# 03_-_POWER_SUPPLIES.net
KiCad netlist of a schematic drawn in Altium Designer
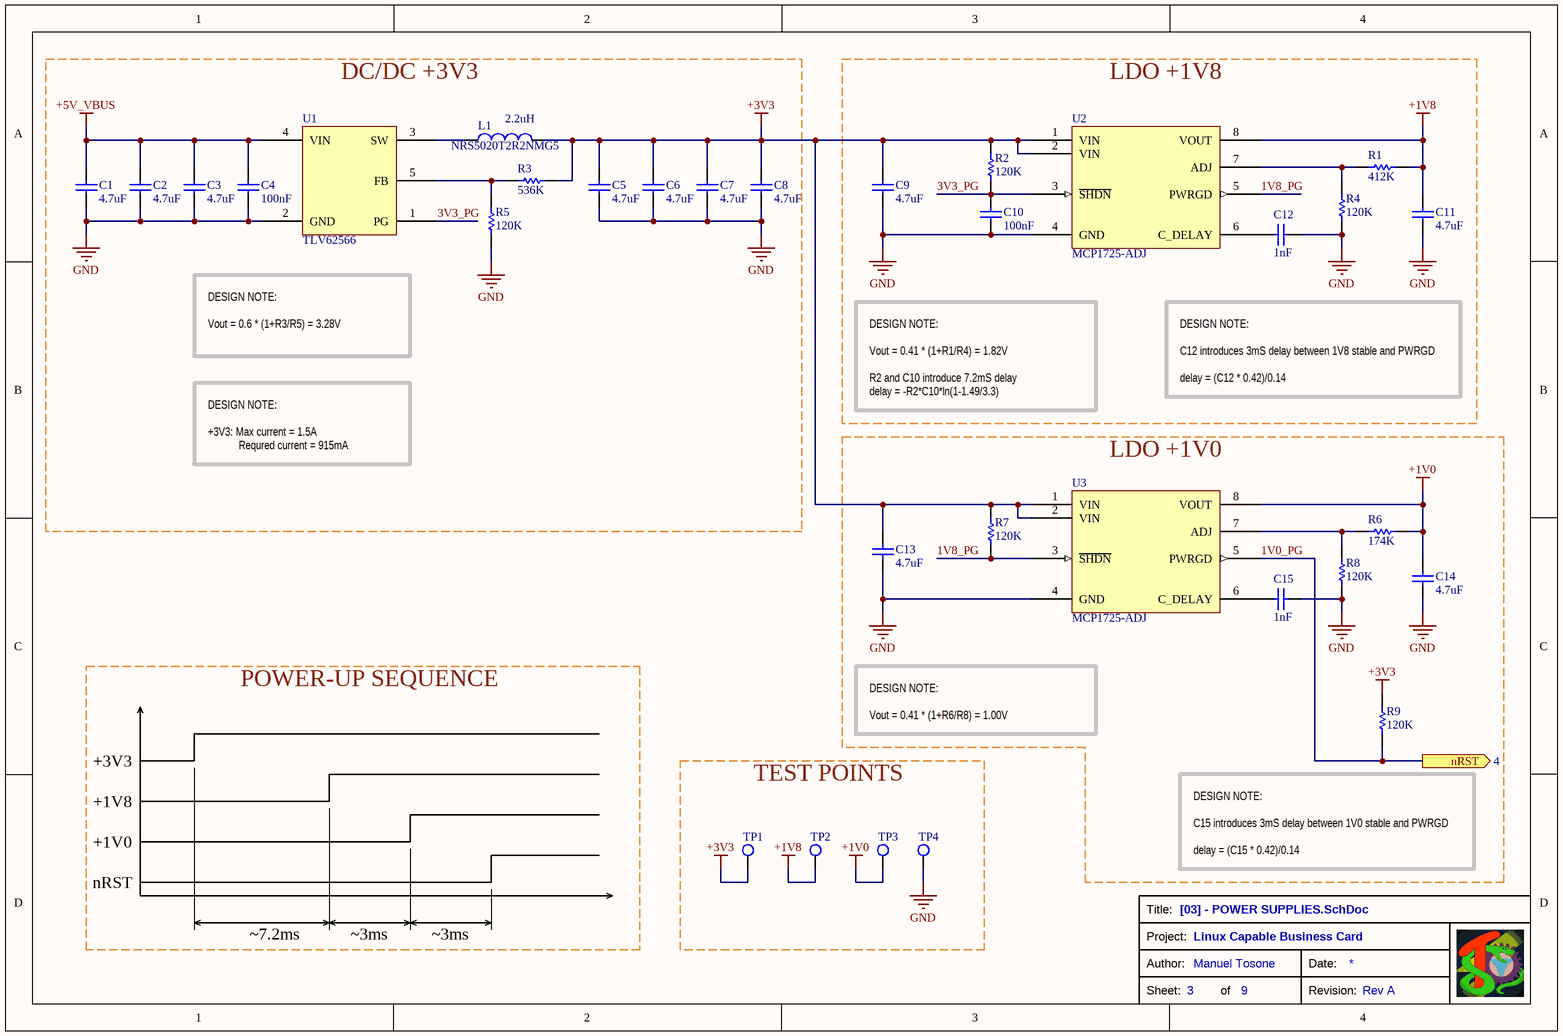
[diagram p0: [03] - POWER SUPPLIES.SchDoc]

(export (version "E")
  (design (tool "Eeschema 10.0.6"))
  (components
    (comp (ref "C1")
      (value "4.7uF")
      (footprint "CAP-0805")
      (description "Multilayer Ceramic Capacitors MLCC - SMD/SMT WCAP-CSGP 4.7uF 0805 20% 16V MLCC")
      (fields (field (name "MANUFACTURER") "Wurth Elektronik") (field (name "Comment") "885012107013"))
      (libsource (lib "Linux-Capable-Business-Card") (part "CAP-0805-4.7u-885012107013_2"))
    )
    (comp (ref "C2")
      (value "4.7uF")
      (footprint "CAP-0805")
      (description "Multilayer Ceramic Capacitors MLCC - SMD/SMT WCAP-CSGP 4.7uF 0805 20% 16V MLCC")
      (fields (field (name "MANUFACTURER") "Wurth Elektronik") (field (name "Comment") "885012107013"))
      (libsource (lib "Linux-Capable-Business-Card") (part "CAP-0805-4.7u-885012107013_2"))
    )
    (comp (ref "C3")
      (value "4.7uF")
      (footprint "CAP-0805")
      (description "Multilayer Ceramic Capacitors MLCC - SMD/SMT WCAP-CSGP 4.7uF 0805 20% 16V MLCC")
      (fields (field (name "MANUFACTURER") "Wurth Elektronik") (field (name "Comment") "885012107013"))
      (libsource (lib "Linux-Capable-Business-Card") (part "CAP-0805-4.7u-885012107013_2"))
    )
    (comp (ref "C4")
      (value "100nF")
      (footprint "CAP-0603")
      (description "Multilayer Ceramic Capacitors MLCC - SMD/SMT 16V 0.1uF X7R 0603 20%")
      (fields (field (name "MANUFACTURER") "KEMET") (field (name "Comment") "C0603C104M4RAC"))
      (libsource (lib "Linux-Capable-Business-Card") (part "CAP-0603-100n-C0603C104M4RAC"))
    )
    (comp (ref "C5")
      (value "4.7uF")
      (footprint "CAP-0805")
      (description "Multilayer Ceramic Capacitors MLCC - SMD/SMT WCAP-CSGP 4.7uF 0805 20% 16V MLCC")
      (fields (field (name "MANUFACTURER") "Wurth Elektronik") (field (name "Comment") "885012107013"))
      (libsource (lib "Linux-Capable-Business-Card") (part "CAP-0805-4.7u-885012107013_2"))
    )
    (comp (ref "C6")
      (value "4.7uF")
      (footprint "CAP-0805")
      (description "Multilayer Ceramic Capacitors MLCC - SMD/SMT WCAP-CSGP 4.7uF 0805 20% 16V MLCC")
      (fields (field (name "MANUFACTURER") "Wurth Elektronik") (field (name "Comment") "885012107013"))
      (libsource (lib "Linux-Capable-Business-Card") (part "CAP-0805-4.7u-885012107013_2"))
    )
    (comp (ref "C7")
      (value "4.7uF")
      (footprint "CAP-0805")
      (description "Multilayer Ceramic Capacitors MLCC - SMD/SMT WCAP-CSGP 4.7uF 0805 20% 16V MLCC")
      (fields (field (name "MANUFACTURER") "Wurth Elektronik") (field (name "Comment") "885012107013"))
      (libsource (lib "Linux-Capable-Business-Card") (part "CAP-0805-4.7u-885012107013_2"))
    )
    (comp (ref "C8")
      (value "4.7uF")
      (footprint "CAP-0805")
      (description "Multilayer Ceramic Capacitors MLCC - SMD/SMT WCAP-CSGP 4.7uF 0805 20% 16V MLCC")
      (fields (field (name "MANUFACTURER") "Wurth Elektronik") (field (name "Comment") "885012107013"))
      (libsource (lib "Linux-Capable-Business-Card") (part "CAP-0805-4.7u-885012107013_2"))
    )
    (comp (ref "C9")
      (value "4.7uF")
      (footprint "CAP-0805")
      (description "Multilayer Ceramic Capacitors MLCC - SMD/SMT WCAP-CSGP 4.7uF 0805 20% 16V MLCC")
      (fields (field (name "MANUFACTURER") "Wurth Elektronik") (field (name "Comment") "885012107013"))
      (libsource (lib "Linux-Capable-Business-Card") (part "CAP-0805-4.7u-885012107013_2"))
    )
    (comp (ref "C10")
      (value "100nF")
      (footprint "CAP-0603")
      (description "Multilayer Ceramic Capacitors MLCC - SMD/SMT 16V 0.1uF X7R 0603 20%")
      (fields (field (name "MANUFACTURER") "KEMET") (field (name "Comment") "C0603C104M4RAC"))
      (libsource (lib "Linux-Capable-Business-Card") (part "CAP-0603-100n-C0603C104M4RAC"))
    )
    (comp (ref "C11")
      (value "4.7uF")
      (footprint "CAP-0805")
      (description "Multilayer Ceramic Capacitors MLCC - SMD/SMT WCAP-CSGP 4.7uF 0805 20% 16V MLCC")
      (fields (field (name "MANUFACTURER") "Wurth Elektronik") (field (name "Comment") "885012107013"))
      (libsource (lib "Linux-Capable-Business-Card") (part "CAP-0805-4.7u-885012107013_2"))
    )
    (comp (ref "C12")
      (value "1nF")
      (footprint "CAP-0603")
      (description "Multilayer Ceramic Capacitors MLCC - SMD/SMT 50V 1000pF X7R 0603 5%")
      (fields (field (name "MANUFACTURER") "KEMET") (field (name "Comment") "C0603C102J5RACTU"))
      (libsource (lib "Linux-Capable-Business-Card") (part "CAP-0603-1n-C0603C102J5RACTU"))
    )
    (comp (ref "C13")
      (value "4.7uF")
      (footprint "CAP-0805")
      (description "Multilayer Ceramic Capacitors MLCC - SMD/SMT WCAP-CSGP 4.7uF 0805 20% 16V MLCC")
      (fields (field (name "MANUFACTURER") "Wurth Elektronik") (field (name "Comment") "885012107013"))
      (libsource (lib "Linux-Capable-Business-Card") (part "CAP-0805-4.7u-885012107013_2"))
    )
    (comp (ref "C14")
      (value "4.7uF")
      (footprint "CAP-0805")
      (description "Multilayer Ceramic Capacitors MLCC - SMD/SMT WCAP-CSGP 4.7uF 0805 20% 16V MLCC")
      (fields (field (name "MANUFACTURER") "Wurth Elektronik") (field (name "Comment") "885012107013"))
      (libsource (lib "Linux-Capable-Business-Card") (part "CAP-0805-4.7u-885012107013_2"))
    )
    (comp (ref "C15")
      (value "1nF")
      (footprint "CAP-0603")
      (description "Multilayer Ceramic Capacitors MLCC - SMD/SMT 50V 1000pF X7R 0603 5%")
      (fields (field (name "MANUFACTURER") "KEMET") (field (name "Comment") "C0603C102J5RACTU"))
      (libsource (lib "Linux-Capable-Business-Card") (part "CAP-0603-1n-C0603C102J5RACTU"))
    )
    (comp (ref "L1")
      (value "NRS5020T2R2NMG5")
      (footprint "NRS5020-SMT-INDUCTOR")
      (description "Fixed Inductors 5020 2.2uH 42mOhms +/-30%Tol 2900mA")
      (fields (field (name "ALTIUM_VALUE") "2.2uH"))
      (libsource (lib "Linux-Capable-Business-Card") (part "IND-NRS5020T2R2NMG5"))
    )
    (comp (ref "R1")
      (value "412K")
      (footprint "RES-0603")
      (description "Thin Film Resistors - SMD 1/10W 412K ohm 1% 50ppm")
      (fields (field (name "MANUFACTURER") "Yageo") (field (name "Comment") "RT0603FRE07412KL"))
      (libsource (lib "Linux-Capable-Business-Card") (part "RES-0603-412K-RT0603FRE07412KL"))
    )
    (comp (ref "R2")
      (value "120K")
      (footprint "RES-0603")
      (description "Thin Film Resistors - SMD 1/10W 120K ohm 1% 50ppm")
      (fields (field (name "MANUFACTURER") "Yageo") (field (name "Comment") "RT0603FRE07120KL"))
      (libsource (lib "Linux-Capable-Business-Card") (part "RES-0603-120K-RT0603FRE07120KL"))
    )
    (comp (ref "R3")
      (value "536K")
      (footprint "RES-0603")
      (description "Thin Film Resistors - SMD 1/10W 536K ohm 1% 50ppm")
      (fields (field (name "MANUFACTURER") "Yageo") (field (name "Comment") "RT0603FRE07536KL"))
      (libsource (lib "Linux-Capable-Business-Card") (part "RES-0603-536K-RT0603FRE07536KL"))
    )
    (comp (ref "R4")
      (value "120K")
      (footprint "RES-0603")
      (description "Thin Film Resistors - SMD 1/10W 120K ohm 1% 50ppm")
      (fields (field (name "MANUFACTURER") "Yageo") (field (name "Comment") "RT0603FRE07120KL"))
      (libsource (lib "Linux-Capable-Business-Card") (part "RES-0603-120K-RT0603FRE07120KL"))
    )
    (comp (ref "R5")
      (value "120K")
      (footprint "RES-0603")
      (description "Thin Film Resistors - SMD 1/10W 120K ohm 1% 50ppm")
      (fields (field (name "MANUFACTURER") "Yageo") (field (name "Comment") "RT0603FRE07120KL"))
      (libsource (lib "Linux-Capable-Business-Card") (part "RES-0603-120K-RT0603FRE07120KL"))
    )
    (comp (ref "R6")
      (value "174K")
      (footprint "RES-0603")
      (description "Thin Film Resistors - SMD 1/10W 174K ohm 1% 50ppm")
      (fields (field (name "MANUFACTURER") "Yageo") (field (name "Comment") "RT0603FRE07174KL"))
      (libsource (lib "Linux-Capable-Business-Card") (part "RES-0603-174K-RT0603FRE07174KL"))
    )
    (comp (ref "R7")
      (value "120K")
      (footprint "RES-0603")
      (description "Thin Film Resistors - SMD 1/10W 120K ohm 1% 50ppm")
      (fields (field (name "MANUFACTURER") "Yageo") (field (name "Comment") "RT0603FRE07120KL"))
      (libsource (lib "Linux-Capable-Business-Card") (part "RES-0603-120K-RT0603FRE07120KL"))
    )
    (comp (ref "R8")
      (value "120K")
      (footprint "RES-0603")
      (description "Thin Film Resistors - SMD 1/10W 120K ohm 1% 50ppm")
      (fields (field (name "MANUFACTURER") "Yageo") (field (name "Comment") "RT0603FRE07120KL"))
      (libsource (lib "Linux-Capable-Business-Card") (part "RES-0603-120K-RT0603FRE07120KL"))
    )
    (comp (ref "R9")
      (value "120K")
      (footprint "RES-0603")
      (description "Thin Film Resistors - SMD 1/10W 120K ohm 1% 50ppm")
      (fields (field (name "MANUFACTURER") "Yageo") (field (name "Comment") "RT0603FRE07120KL"))
      (libsource (lib "Linux-Capable-Business-Card") (part "RES-0603-120K-RT0603FRE07120KL"))
    )
    (comp (ref "TP1")
      (value "Test Point 1mm")
      (footprint "TESTPOINT-1mm")
      (libsource (lib "Linux-Capable-Business-Card") (part "TESTPOINT-1mm"))
    )
    (comp (ref "TP2")
      (value "Test Point 1mm")
      (footprint "TESTPOINT-1mm")
      (libsource (lib "Linux-Capable-Business-Card") (part "TESTPOINT-1mm"))
    )
    (comp (ref "TP3")
      (value "Test Point 1mm")
      (footprint "TESTPOINT-1mm")
      (libsource (lib "Linux-Capable-Business-Card") (part "TESTPOINT-1mm"))
    )
    (comp (ref "TP4")
      (value "Test Point 1mm")
      (footprint "TESTPOINT-1mm")
      (libsource (lib "Linux-Capable-Business-Card") (part "TESTPOINT-1mm"))
    )
    (comp (ref "U1")
      (value "TLV62566")
      (footprint "SOT23-5")
      (description "TLV6256x 1.5-A High Efficiency Step-Down Converters in SOT-23 5-Pin Package")
      (libsource (lib "Linux-Capable-Business-Card") (part "TLV62566"))
    )
    (comp (ref "U2")
      (value "MCP1725-ADJ")
      (footprint "SOIC-8_3.9X4.9")
      (description "500 mA, Low Voltage, Low Quiescent Current LDO Regulator")
      (libsource (lib "Linux-Capable-Business-Card") (part "MCP1725-ADJ"))
    )
    (comp (ref "U3")
      (value "MCP1725-ADJ")
      (footprint "SOIC-8_3.9X4.9")
      (description "500 mA, Low Voltage, Low Quiescent Current LDO Regulator")
      (libsource (lib "Linux-Capable-Business-Card") (part "MCP1725-ADJ"))
    )
  )
  (nets
    (net (code "1") (name "+1V0") (class "Default")
      (node (ref "C14") (pin "2") (pinfunction "2_2") (pintype "passive"))
      (node (ref "R6") (pin "2") (pinfunction "2_2") (pintype "passive"))
      (node (ref "TP3") (pin "1") (pinfunction "1_1") (pintype "passive"))
      (node (ref "U3") (pin "8") (pinfunction "VOUT_8") (pintype "power_in"))
    )
    (net (code "2") (name "+1V8") (class "Default")
      (node (ref "C11") (pin "2") (pinfunction "2_2") (pintype "passive"))
      (node (ref "R1") (pin "2") (pinfunction "2_2") (pintype "passive"))
      (node (ref "TP2") (pin "1") (pinfunction "1_1") (pintype "passive"))
      (node (ref "U2") (pin "8") (pinfunction "VOUT_8") (pintype "power_in"))
    )
    (net (code "3") (name "+3V3") (class "Default")
      (node (ref "C13") (pin "2") (pinfunction "2_2") (pintype "passive"))
      (node (ref "C5") (pin "2") (pinfunction "2_2") (pintype "passive"))
      (node (ref "C6") (pin "2") (pinfunction "2_2") (pintype "passive"))
      (node (ref "C7") (pin "2") (pinfunction "2_2") (pintype "passive"))
      (node (ref "C8") (pin "2") (pinfunction "2_2") (pintype "passive"))
      (node (ref "C9") (pin "2") (pinfunction "2_2") (pintype "passive"))
      (node (ref "L1") (pin "2") (pinfunction "2_2") (pintype "passive"))
      (node (ref "R2") (pin "2") (pinfunction "2_2") (pintype "passive"))
      (node (ref "R3") (pin "1") (pinfunction "1_1") (pintype "passive"))
      (node (ref "R7") (pin "2") (pinfunction "2_2") (pintype "passive"))
      (node (ref "R9") (pin "2") (pinfunction "2_2") (pintype "passive"))
      (node (ref "TP1") (pin "1") (pinfunction "1_1") (pintype "passive"))
      (node (ref "U2") (pin "1") (pinfunction "VIN_1") (pintype "power_in"))
      (node (ref "U2") (pin "2") (pinfunction "VIN_2") (pintype "power_in"))
      (node (ref "U3") (pin "1") (pinfunction "VIN_1") (pintype "power_in"))
      (node (ref "U3") (pin "2") (pinfunction "VIN_2") (pintype "power_in"))
    )
    (net (code "4") (name "+5V_VBUS") (class "Default")
      (node (ref "C1") (pin "2") (pinfunction "2_2") (pintype "passive"))
      (node (ref "C2") (pin "2") (pinfunction "2_2") (pintype "passive"))
      (node (ref "C3") (pin "2") (pinfunction "2_2") (pintype "passive"))
      (node (ref "C4") (pin "2") (pinfunction "2_2") (pintype "passive"))
      (node (ref "U1") (pin "4") (pinfunction "VIN_4") (pintype "power_in"))
    )
    (net (code "5") (name "/1V0_PG") (class "Default")
      (node (ref "R9") (pin "1") (pinfunction "1_1") (pintype "passive"))
      (node (ref "U3") (pin "5") (pinfunction "PWRGD_5") (pintype "output"))
    )
    (net (code "6") (name "/1V8_PG") (class "Default")
      (node (ref "R7") (pin "1") (pinfunction "1_1") (pintype "passive"))
      (node (ref "U2") (pin "5") (pinfunction "PWRGD_5") (pintype "output"))
      (node (ref "U3") (pin "3") (pinfunction "~{SHDN}_3") (pintype "input"))
    )
    (net (code "7") (name "/3V3_PG") (class "Default")
      (node (ref "C10") (pin "2") (pinfunction "2_2") (pintype "passive"))
      (node (ref "R2") (pin "1") (pinfunction "1_1") (pintype "passive"))
      (node (ref "U1") (pin "1") (pinfunction "PG_1") (pintype "passive"))
      (node (ref "U2") (pin "3") (pinfunction "~{SHDN}_3") (pintype "input"))
    )
    (net (code "8") (name "GND") (class "Default")
      (node (ref "C1") (pin "1") (pinfunction "1_1") (pintype "passive"))
      (node (ref "C10") (pin "1") (pinfunction "1_1") (pintype "passive"))
      (node (ref "C11") (pin "1") (pinfunction "1_1") (pintype "passive"))
      (node (ref "C12") (pin "1") (pinfunction "1_1") (pintype "passive"))
      (node (ref "C13") (pin "1") (pinfunction "1_1") (pintype "passive"))
      (node (ref "C14") (pin "1") (pinfunction "1_1") (pintype "passive"))
      (node (ref "C15") (pin "1") (pinfunction "1_1") (pintype "passive"))
      (node (ref "C2") (pin "1") (pinfunction "1_1") (pintype "passive"))
      (node (ref "C3") (pin "1") (pinfunction "1_1") (pintype "passive"))
      (node (ref "C4") (pin "1") (pinfunction "1_1") (pintype "passive"))
      (node (ref "C5") (pin "1") (pinfunction "1_1") (pintype "passive"))
      (node (ref "C6") (pin "1") (pinfunction "1_1") (pintype "passive"))
      (node (ref "C7") (pin "1") (pinfunction "1_1") (pintype "passive"))
      (node (ref "C8") (pin "1") (pinfunction "1_1") (pintype "passive"))
      (node (ref "C9") (pin "1") (pinfunction "1_1") (pintype "passive"))
      (node (ref "R4") (pin "1") (pinfunction "1_1") (pintype "passive"))
      (node (ref "R5") (pin "1") (pinfunction "1_1") (pintype "passive"))
      (node (ref "R8") (pin "1") (pinfunction "1_1") (pintype "passive"))
      (node (ref "TP4") (pin "1") (pinfunction "1_1") (pintype "passive"))
      (node (ref "U1") (pin "2") (pinfunction "GND_2") (pintype "power_in"))
      (node (ref "U2") (pin "4") (pinfunction "GND_4") (pintype "power_in"))
      (node (ref "U3") (pin "4") (pinfunction "GND_4") (pintype "power_in"))
    )
    (net (code "9") (name "Net-(U1-FB)") (class "Default")
      (node (ref "R3") (pin "2") (pinfunction "2_2") (pintype "passive"))
      (node (ref "R5") (pin "2") (pinfunction "2_2") (pintype "passive"))
      (node (ref "U1") (pin "5") (pinfunction "FB_5") (pintype "passive"))
    )
    (net (code "10") (name "Net-(U1-SW)") (class "Default")
      (node (ref "L1") (pin "1") (pinfunction "1_1") (pintype "passive"))
      (node (ref "U1") (pin "3") (pinfunction "SW_3") (pintype "passive"))
    )
    (net (code "11") (name "Net-(U2-ADJ)") (class "Default")
      (node (ref "R1") (pin "1") (pinfunction "1_1") (pintype "passive"))
      (node (ref "R4") (pin "2") (pinfunction "2_2") (pintype "passive"))
      (node (ref "U2") (pin "7") (pinfunction "ADJ_7") (pintype "passive"))
    )
    (net (code "12") (name "Net-(U2-C_DELAY)") (class "Default")
      (node (ref "C12") (pin "2") (pinfunction "2_2") (pintype "passive"))
      (node (ref "U2") (pin "6") (pinfunction "C_DELAY_6") (pintype "passive"))
    )
    (net (code "13") (name "Net-(U3-ADJ)") (class "Default")
      (node (ref "R6") (pin "1") (pinfunction "1_1") (pintype "passive"))
      (node (ref "R8") (pin "2") (pinfunction "2_2") (pintype "passive"))
      (node (ref "U3") (pin "7") (pinfunction "ADJ_7") (pintype "passive"))
    )
    (net (code "14") (name "Net-(U3-C_DELAY)") (class "Default")
      (node (ref "C15") (pin "2") (pinfunction "2_2") (pintype "passive"))
      (node (ref "U3") (pin "6") (pinfunction "C_DELAY_6") (pintype "passive"))
    )
  )
)
